# primary_EEPROM_and_T.net
KiCad netlist of a schematic drawn in Altium Designer
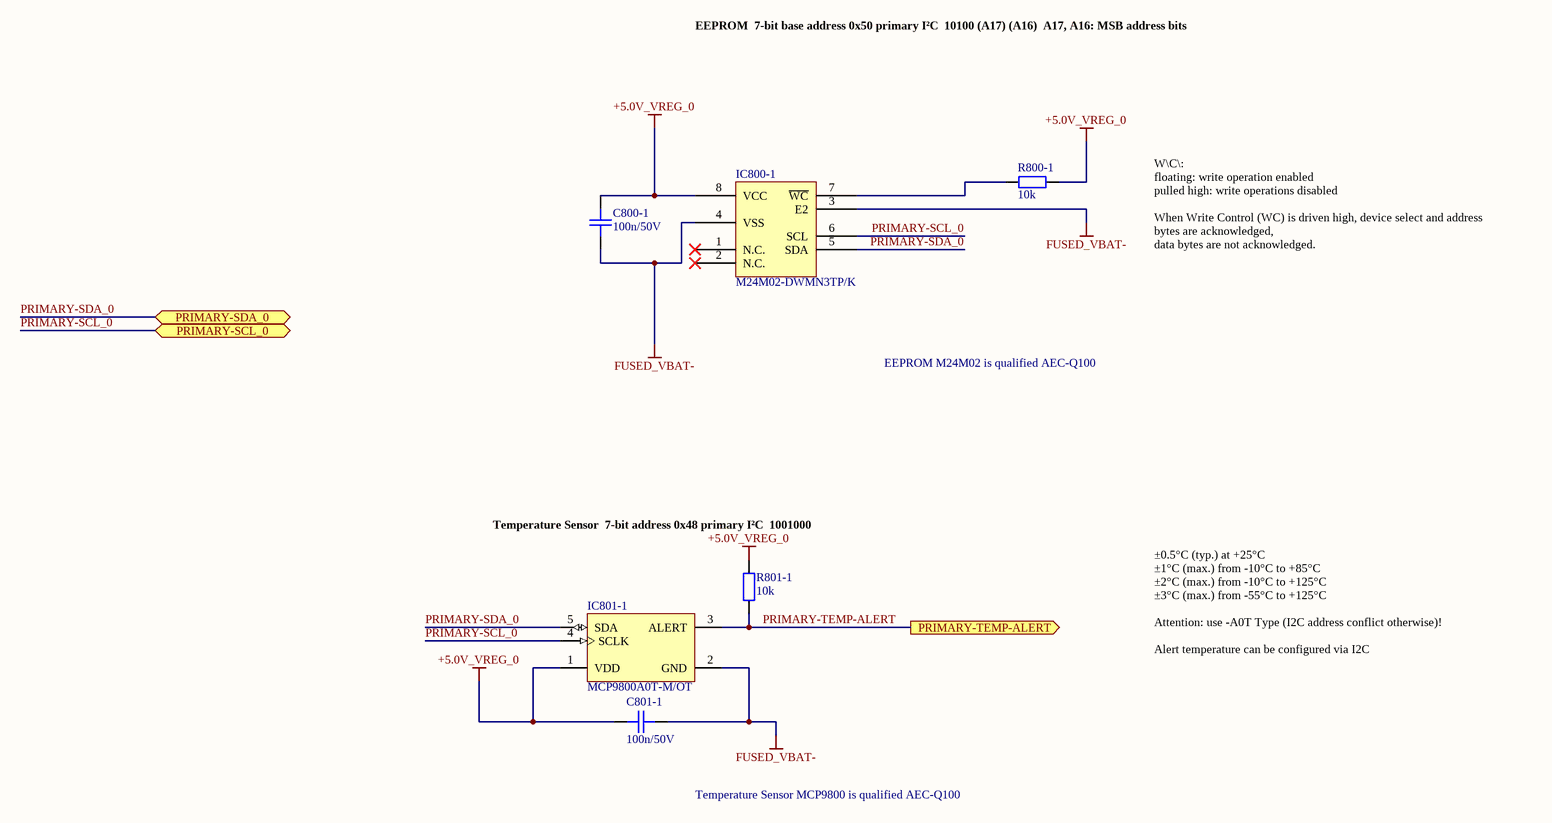
[diagram p0: primary_EEPROM_and_T.SchDoc]

(export (version "E")
  (design (tool "Eeschema 10.0.6"))
  (components
    (comp (ref "C800-1")
      (value "100n/50V")
      (footprint "CAPC1608X08N")
      (description "MLCC")
      (fields (field (name "PART NUMBER") "gen_C_ceramic_100n_50V_X7R_0603"))
      (libsource (lib "OE750") (part "C"))
    )
    (comp (ref "C801-1")
      (value "100n/50V")
      (footprint "CAPC1608X08N")
      (description "MLCC")
      (fields (field (name "PART NUMBER") "gen_C_ceramic_100n_50V_X7R_0603"))
      (libsource (lib "OE750") (part "C"))
    )
    (comp (ref "IC800-1")
      (value "M24M02-DWMN3TP/K")
      (footprint "SOIC127P600X175-8N")
      (description "Automotive 2-Mbit serial I²C \r\nbus EEPROM with 1 MHz clock")
      (fields (field (name "MANUFACTURER") "STMicroelectronics"))
      (libsource (lib "OE750") (part "M24M02-DWMN3TP/K"))
    )
    (comp (ref "IC801-1")
      (value "MCP9800A0T-M/OT")
      (footprint "SOT-23-OT5_L")
      (libsource (lib "Altium Content Vault") (part "SEN-TEMP-MCP980X-5"))
    )
    (comp (ref "R800-1")
      (value "10k")
      (footprint "RESC1608X05N")
      (description "SMD Resistor 10k 0603")
      (fields (field (name "PART NUMBER") "gen_R_10k_0603") (field (name "TOLERANCE") "1%"))
      (libsource (lib "OE750") (part "R"))
    )
    (comp (ref "R801-1")
      (value "10k")
      (footprint "RESC1608X05N")
      (description "SMD Resistor 10k 0603")
      (fields (field (name "PART NUMBER") "gen_R_10k_0603") (field (name "TOLERANCE") "1%"))
      (libsource (lib "OE750") (part "R"))
    )
  )
  (nets
    (net (code "1") (name "+5.0V_VREG_0") (class "Default")
      (node (ref "C800-1") (pin "2") (pinfunction "2_2") (pintype "passive"))
      (node (ref "C801-1") (pin "2") (pinfunction "2_2") (pintype "passive"))
      (node (ref "IC800-1") (pin "8") (pinfunction "VCC_8") (pintype "power_in"))
      (node (ref "IC801-1") (pin "1") (pinfunction "VDD_1") (pintype "power_in"))
      (node (ref "R800-1") (pin "2") (pinfunction "2_2") (pintype "passive"))
      (node (ref "R801-1") (pin "2") (pinfunction "2_2") (pintype "passive"))
    )
    (net (code "2") (name "/PRIMARY-SCL_0") (class "Default")
      (node (ref "IC800-1") (pin "6") (pinfunction "SCL_6") (pintype "passive"))
      (node (ref "IC801-1") (pin "4") (pinfunction "SCLK_4") (pintype "input"))
    )
    (net (code "3") (name "/PRIMARY-SDA_0") (class "Default")
      (node (ref "IC800-1") (pin "5") (pinfunction "SDA_5") (pintype "passive"))
      (node (ref "IC801-1") (pin "5") (pinfunction "SDA_5") (pintype "bidirectional"))
    )
    (net (code "4") (name "/PRIMARY-TEMP-ALERT") (class "Default")
      (node (ref "IC801-1") (pin "3") (pinfunction "ALERT_3") (pintype "open_collector"))
      (node (ref "R801-1") (pin "1") (pinfunction "1_1") (pintype "passive"))
    )
    (net (code "5") (name "FUSED_VBAT-") (class "Default")
      (node (ref "C800-1") (pin "1") (pinfunction "1_1") (pintype "passive"))
      (node (ref "C801-1") (pin "1") (pinfunction "1_1") (pintype "passive"))
      (node (ref "IC800-1") (pin "3") (pinfunction "E2_3") (pintype "passive"))
      (node (ref "IC800-1") (pin "4") (pinfunction "VSS_4") (pintype "power_in"))
      (node (ref "IC801-1") (pin "2") (pinfunction "GND_2") (pintype "power_in"))
    )
    (net (code "6") (name "Net-(IC800-1-~{WC})") (class "Default")
      (node (ref "IC800-1") (pin "7") (pinfunction "~{WC}_7") (pintype "passive"))
      (node (ref "R800-1") (pin "1") (pinfunction "1_1") (pintype "passive"))
    )
    (net (code "7") (name "unconnected-(IC800-1-N.C.-Pad1)") (class "Default")
      (node (ref "IC800-1") (pin "1") (pinfunction "N.C._1") (pintype "passive+no_connect"))
    )
    (net (code "8") (name "unconnected-(IC800-1-N.C.-Pad2)") (class "Default")
      (node (ref "IC800-1") (pin "2") (pinfunction "N.C._2") (pintype "passive+no_connect"))
    )
  )
)
